# schematic_EN15.net
KiCad netlist of a schematic drawn in Altium Designer
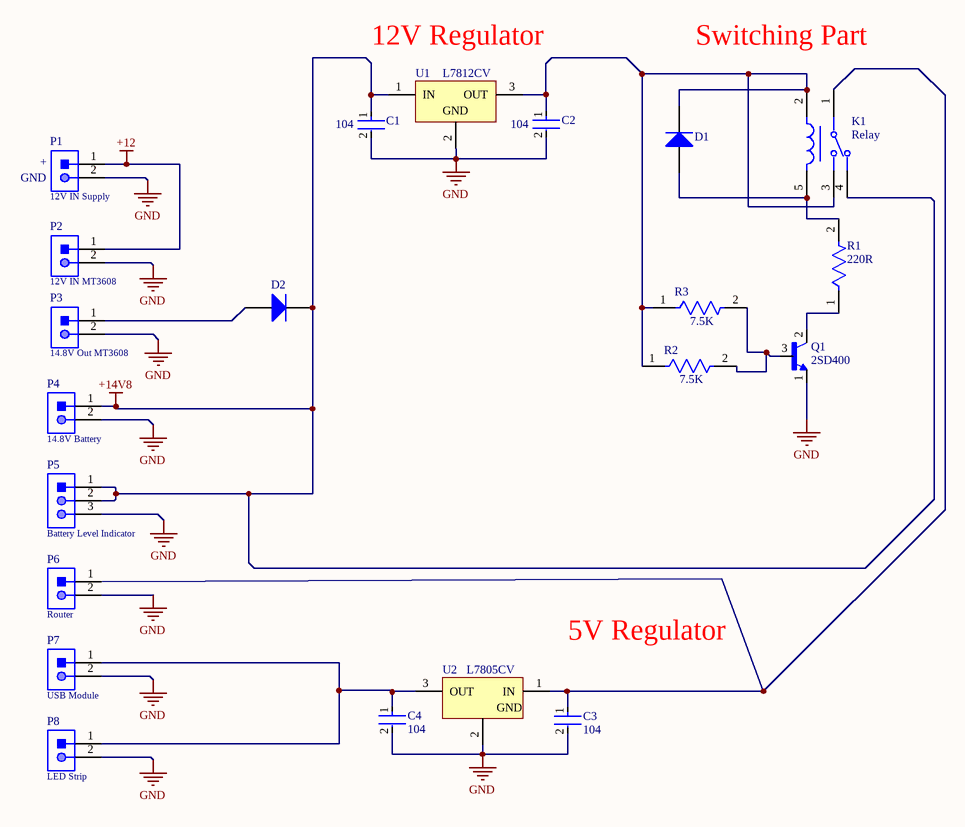
[diagram p0: schematic EN15.SchDoc]

(export (version "E")
  (design (tool "Eeschema 10.0.6"))
  (components
    (comp (ref "C1")
      (value "104")
      (footprint "FP-RCE0K1-MFG")
      (description "Cap Ceramic 1pF 100V C0G ±0.25pF Radial 5mm +125°C Automotive Bulk")
      (libsource (lib "Altium Content Vault") (part "b4654b650e69147ec39a6b967a45e02"))
    )
    (comp (ref "C2")
      (value "104")
      (footprint "FP-RCE0K1-MFG")
      (description "Cap Ceramic 1pF 100V C0G ±0.25pF Radial 5mm +125°C Automotive Bulk")
      (libsource (lib "Altium Content Vault") (part "b4654b650e69147ec39a6b967a45e02"))
    )
    (comp (ref "C3")
      (value "104")
      (footprint "FP-RCE0K1-MFG")
      (description "Cap Ceramic 1pF 100V C0G ±0.25pF Radial 5mm +125°C Automotive Bulk")
      (libsource (lib "Altium Content Vault") (part "b4654b650e69147ec39a6b967a45e02"))
    )
    (comp (ref "C4")
      (value "104")
      (footprint "FP-RCE0K1-MFG")
      (description "Cap Ceramic 1pF 100V C0G ±0.25pF Radial 5mm +125°C Automotive Bulk")
      (libsource (lib "Altium Content Vault") (part "b4654b650e69147ec39a6b967a45e02"))
    )
    (comp (ref "D1")
      (value "Diode 1N4001")
      (footprint "DO-41")
      (description "1 Amp General Purpose Rectifier")
      (fields (field (name "PUBLISHER") "Altium Limited"))
      (libsource (lib "Miscellaneous Devices") (part "Diode 1N4001"))
    )
    (comp (ref "D2")
      (value "Diode 1N4001")
      (footprint "DO-41")
      (description "1 Amp General Purpose Rectifier")
      (fields (field (name "PUBLISHER") "Altium Limited"))
      (libsource (lib "Miscellaneous Devices") (part "Diode 1N4001"))
    )
    (comp (ref "K1")
      (value "Relay")
      (footprint "FP-JS1-5V-F-MFG")
      (description "RELAY GEN PURPOSE SPDT 10A 5V")
      (fields
        (field (name "MANUFACTURER PART NUMBER") "JS1-5V-F")
        (field (name "OCTOPART") "https://octopart.com/js1-5v-f-panasonic-39428621")
      )
      (libsource (lib "Altium Content Vault") (part "250623531296f86beaf95f2bc4a6d4c"))
    )
    (comp (ref "P1")
      (value "12V IN Supply")
      (footprint "61300211121")
      (description "THT Vertical Pin Header WR-PHD, Pitch 2.54 mm, Single Row, 2 pins")
      (fields
        (field (name "MANUFACTURER") "Wurth Elektronik")
        (field (name "PART NUMBER") "61300211121")
        (field (name "PUBLISHER") "WurthElektronik")
      )
      (libsource (lib "Altium Content Vault") (part "WE-CN-1P-M-R2"))
    )
    (comp (ref "P2")
      (value "12V IN MT3608")
      (footprint "61300211121")
      (description "THT Vertical Pin Header WR-PHD, Pitch 2.54 mm, Single Row, 2 pins")
      (fields
        (field (name "MANUFACTURER") "Wurth Elektronik")
        (field (name "PART NUMBER") "61300211121")
        (field (name "PUBLISHER") "WurthElektronik")
      )
      (libsource (lib "Altium Content Vault") (part "WE-CN-1P-M-R2"))
    )
    (comp (ref "P3")
      (value "14.8V Out MT3608")
      (footprint "61300211121")
      (description "THT Vertical Pin Header WR-PHD, Pitch 2.54 mm, Single Row, 2 pins")
      (fields
        (field (name "MANUFACTURER") "Wurth Elektronik")
        (field (name "PART NUMBER") "61300211121")
        (field (name "PUBLISHER") "WurthElektronik")
      )
      (libsource (lib "Altium Content Vault") (part "WE-CN-1P-M-R2"))
    )
    (comp (ref "P4")
      (value "14.8V Battery")
      (footprint "61300211121")
      (description "THT Vertical Pin Header WR-PHD, Pitch 2.54 mm, Single Row, 2 pins")
      (fields
        (field (name "MANUFACTURER") "Wurth Elektronik")
        (field (name "PART NUMBER") "61300211121")
        (field (name "PUBLISHER") "WurthElektronik")
      )
      (libsource (lib "Altium Content Vault") (part "WE-CN-1P-M-R2"))
    )
    (comp (ref "P5")
      (value "Battery Level Indicator")
      (footprint "61900319521")
      (description "Male Top Locking Header WR-WTB, THT, Right Angled, pitch 2.54 mm, 1 x 3 position")
      (fields
        (field (name "PART NUMBER") "61900319521")
        (field (name "MANUFACTURER") "Wurth Elektronik")
        (field (name "PUBLISHER") "WurthElektronik")
      )
      (libsource (lib "Altium Content Vault") (part "WE-CN-1P-M-R3"))
    )
    (comp (ref "P6")
      (value "Router")
      (footprint "61300211121")
      (description "THT Vertical Pin Header WR-PHD, Pitch 2.54 mm, Single Row, 2 pins")
      (fields
        (field (name "MANUFACTURER") "Wurth Elektronik")
        (field (name "PART NUMBER") "61300211121")
        (field (name "PUBLISHER") "WurthElektronik")
      )
      (libsource (lib "Altium Content Vault") (part "WE-CN-1P-M-R2"))
    )
    (comp (ref "P7")
      (value "USB Module")
      (footprint "61300211121")
      (description "THT Vertical Pin Header WR-PHD, Pitch 2.54 mm, Single Row, 2 pins")
      (fields
        (field (name "MANUFACTURER") "Wurth Elektronik")
        (field (name "PART NUMBER") "61300211121")
        (field (name "PUBLISHER") "WurthElektronik")
      )
      (libsource (lib "Altium Content Vault") (part "WE-CN-1P-M-R2"))
    )
    (comp (ref "P8")
      (value "LED Strip")
      (footprint "61300211121")
      (description "THT Vertical Pin Header WR-PHD, Pitch 2.54 mm, Single Row, 2 pins")
      (fields
        (field (name "MANUFACTURER") "Wurth Elektronik")
        (field (name "PART NUMBER") "61300211121")
        (field (name "PUBLISHER") "WurthElektronik")
      )
      (libsource (lib "Altium Content Vault") (part "WE-CN-1P-M-R2"))
    )
    (comp (ref "Q1")
      (value "2SD400")
      (footprint "TO145P470X600X850-3P")
      (description "Connector Header Through Hole 20 position 0.100 _2.54mm_")
      (fields (field (name "MF") "Samtec Inc."))
      (libsource (lib "2SD400") (part "2SD400"))
    )
    (comp (ref "R1")
      (value "PCF14JT7K50")
      (footprint "FP-CF14-MFG")
      (description "RES 7.5K OHM 1/4W 5% AXIAL")
      (fields (field (name "RESISTANCE") "220R") (field (name "TOLERANCE") "5%"))
      (libsource (lib "Altium Content Vault") (part "1029c3af85768c4190bb7ad29bc67b5"))
    )
    (comp (ref "R2")
      (value "PCF14JT7K50")
      (footprint "FP-CF14-MFG")
      (description "RES 7.5K OHM 1/4W 5% AXIAL")
      (fields (field (name "RESISTANCE") "7.5K") (field (name "TOLERANCE") "5%"))
      (libsource (lib "Altium Content Vault") (part "1029c3af85768c4190bb7ad29bc67b5"))
    )
    (comp (ref "R3")
      (value "PCF14JT7K50")
      (footprint "FP-CF14-MFG")
      (description "RES 7.5K OHM 1/4W 5% AXIAL")
      (fields (field (name "RESISTANCE") "7.5K") (field (name "TOLERANCE") "5%"))
      (libsource (lib "Altium Content Vault") (part "1029c3af85768c4190bb7ad29bc67b5"))
    )
    (comp (ref "U1")
      (value "L7812CV")
      (footprint "TO220")
      (description "Positive Voltage Regulator, 12V, 3-Pin TO-220")
      (libsource (lib "") (part "PM-REG-L4940-SIL3_1"))
    )
    (comp (ref "U2")
      (value "L7805CV")
      (footprint "TO220")
      (description "Positive Voltage Regulator, 5V, 3-Pin TO-220")
      (libsource (lib "Altium Content Vault") (part "PM-REG-L4940-SIL3"))
    )
  )
  (nets
    (net (code "1") (name "+12") (class "Default")
      (node (ref "P1") (pin "1") (pinfunction "1_1") (pintype "passive"))
      (node (ref "P2") (pin "1") (pinfunction "1_1") (pintype "passive"))
    )
    (net (code "2") (name "+14V8") (class "Default")
      (node (ref "C1") (pin "1") (pinfunction "1_1") (pintype "passive"))
      (node (ref "D2") (pin "2") (pinfunction "K_2") (pintype "passive"))
      (node (ref "K1") (pin "4") (pinfunction "N.C._4") (pintype "passive"))
      (node (ref "P4") (pin "1") (pinfunction "1_1") (pintype "passive"))
      (node (ref "P5") (pin "1") (pinfunction "1_1") (pintype "passive"))
      (node (ref "P5") (pin "2") (pinfunction "2_2") (pintype "passive"))
      (node (ref "U1") (pin "1") (pinfunction "IN_1") (pintype "power_in"))
    )
    (net (code "3") (name "GND") (class "Default")
      (node (ref "C1") (pin "2") (pinfunction "2_2") (pintype "passive"))
      (node (ref "C2") (pin "2") (pinfunction "2_2") (pintype "passive"))
      (node (ref "C3") (pin "2") (pinfunction "2_2") (pintype "passive"))
      (node (ref "C4") (pin "2") (pinfunction "2_2") (pintype "passive"))
      (node (ref "P1") (pin "2") (pinfunction "2_2") (pintype "passive"))
      (node (ref "P2") (pin "2") (pinfunction "2_2") (pintype "passive"))
      (node (ref "P3") (pin "2") (pinfunction "2_2") (pintype "passive"))
      (node (ref "P4") (pin "2") (pinfunction "2_2") (pintype "passive"))
      (node (ref "P5") (pin "3") (pinfunction "3_3") (pintype "passive"))
      (node (ref "P6") (pin "2") (pinfunction "2_2") (pintype "passive"))
      (node (ref "P7") (pin "2") (pinfunction "2_2") (pintype "passive"))
      (node (ref "P8") (pin "2") (pinfunction "2_2") (pintype "passive"))
      (node (ref "Q1") (pin "1") (pinfunction "E_1") (pintype "passive"))
      (node (ref "U1") (pin "2") (pinfunction "GND_2") (pintype "power_in"))
      (node (ref "U2") (pin "2") (pinfunction "GND_2") (pintype "power_in"))
    )
    (net (code "4") (name "Net-(D1-A)") (class "Default")
      (node (ref "D1") (pin "1") (pinfunction "A_1") (pintype "passive"))
      (node (ref "K1") (pin "5") (pinfunction "2_COIL_5") (pintype "passive"))
      (node (ref "R1") (pin "2") (pinfunction "2_2") (pintype "passive"))
    )
    (net (code "5") (name "Net-(D1-K)") (class "Default")
      (node (ref "C2") (pin "1") (pinfunction "1_1") (pintype "passive"))
      (node (ref "D1") (pin "2") (pinfunction "K_2") (pintype "passive"))
      (node (ref "K1") (pin "2") (pinfunction "1_COIL_2") (pintype "passive"))
      (node (ref "K1") (pin "3") (pinfunction "N.O._3") (pintype "passive"))
      (node (ref "R2") (pin "1") (pinfunction "1_1") (pintype "passive"))
      (node (ref "R3") (pin "1") (pinfunction "1_1") (pintype "passive"))
      (node (ref "U1") (pin "3") (pinfunction "OUT_3") (pintype "power_in"))
    )
    (net (code "6") (name "Net-(D2-A)") (class "Default")
      (node (ref "D2") (pin "1") (pinfunction "A_1") (pintype "passive"))
      (node (ref "P3") (pin "1") (pinfunction "1_1") (pintype "passive"))
    )
    (net (code "7") (name "Net-(K1-COM)") (class "Default")
      (node (ref "C3") (pin "1") (pinfunction "1_1") (pintype "passive"))
      (node (ref "K1") (pin "1") (pinfunction "COM_1") (pintype "passive"))
      (node (ref "P6") (pin "1") (pinfunction "1_1") (pintype "passive"))
      (node (ref "U2") (pin "1") (pinfunction "IN_1") (pintype "power_in"))
    )
    (net (code "8") (name "Net-(Q1-B)") (class "Default")
      (node (ref "Q1") (pin "3") (pinfunction "B_3") (pintype "passive"))
      (node (ref "R2") (pin "2") (pinfunction "2_2") (pintype "passive"))
      (node (ref "R3") (pin "2") (pinfunction "2_2") (pintype "passive"))
    )
    (net (code "9") (name "Net-(Q1-C)") (class "Default")
      (node (ref "Q1") (pin "2") (pinfunction "C_2") (pintype "passive"))
      (node (ref "R1") (pin "1") (pinfunction "1_1") (pintype "passive"))
    )
    (net (code "10") (name "Net-(U2-OUT)") (class "Default")
      (node (ref "C4") (pin "1") (pinfunction "1_1") (pintype "passive"))
      (node (ref "P7") (pin "1") (pinfunction "1_1") (pintype "passive"))
      (node (ref "P8") (pin "1") (pinfunction "1_1") (pintype "passive"))
      (node (ref "U2") (pin "3") (pinfunction "OUT_3") (pintype "power_in"))
    )
  )
)
